# NachtElk_DBL_PowerDistribution_3V3-5V.net
KiCad netlist of a schematic drawn in EAGLE
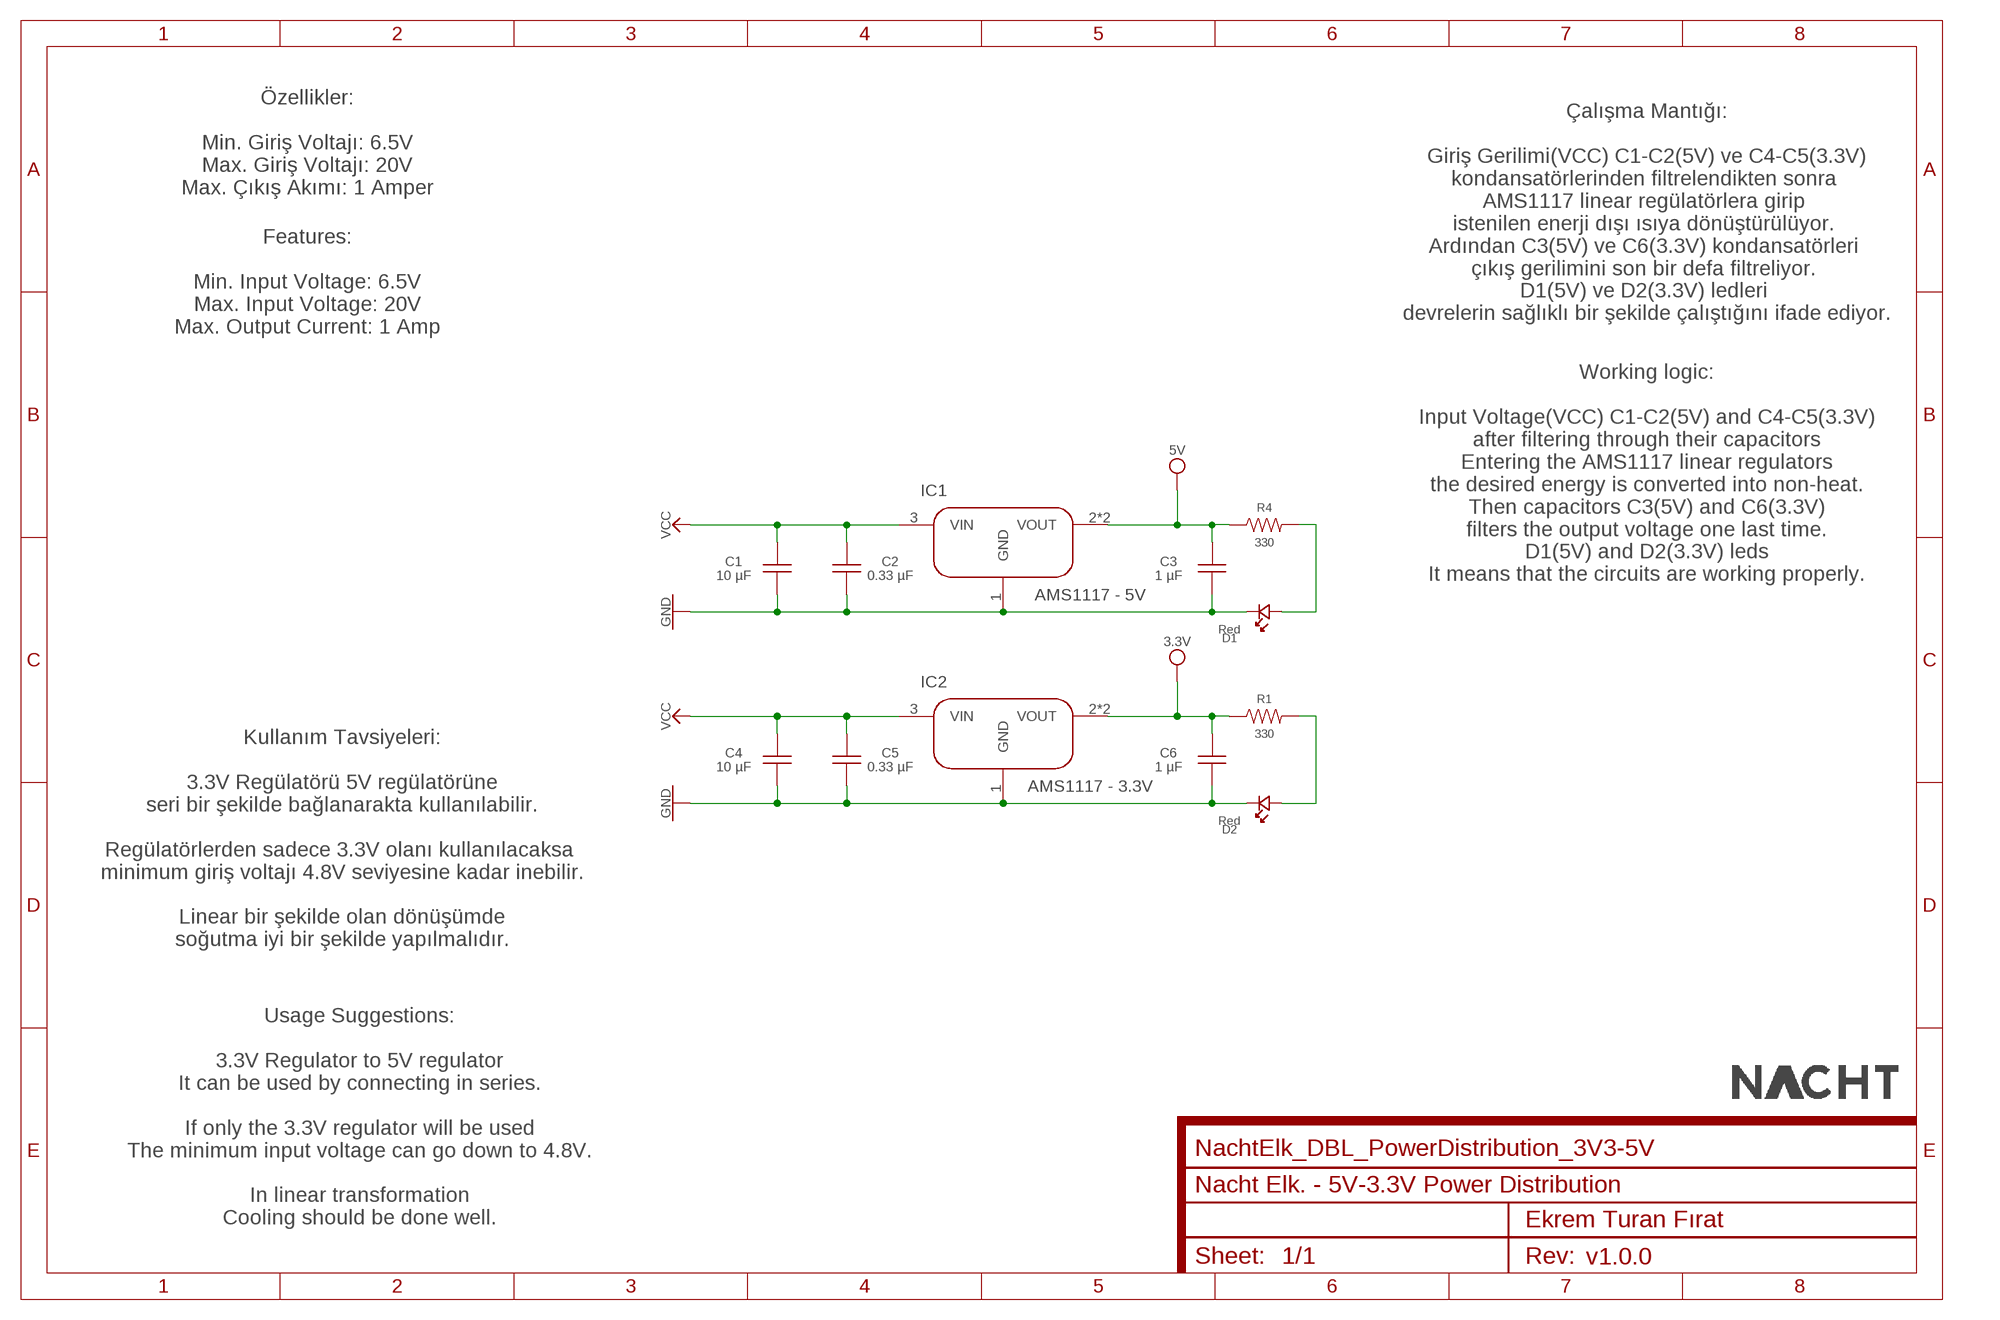
[diagram p0: schematic, sheet 1]

(export (version "E")
  (design (tool "Eeschema 10.0.6"))
  (components
    (comp (ref "C1")
      (value "10 µF")
      (footprint "eagle-import:0603")
      (fields (field (name "TOLERANCE") "10%") (field (name "VOLTAGE") "25V"))
      (libsource (lib "eagle-import") (part "NACHTELK_CAP-NONPOLAR-SMD_0603_10UF"))
    )
    (comp (ref "C2")
      (value "0.33 µF")
      (footprint "eagle-import:0603")
      (fields (field (name "TOLERANCE") "10%") (field (name "VOLTAGE") "50V"))
      (libsource (lib "eagle-import") (part "NACHTELK_CAP-NONPOLAR-SMD_0603_0.33UF"))
    )
    (comp (ref "C3")
      (value "1 µF")
      (footprint "eagle-import:0603")
      (fields (field (name "TOLERANCE") "10%") (field (name "VOLTAGE") "50V"))
      (libsource (lib "eagle-import") (part "NACHTELK_CAP-NONPOLAR-SMD_0603_1UF"))
    )
    (comp (ref "C4")
      (value "10 µF")
      (footprint "eagle-import:0603")
      (fields (field (name "TOLERANCE") "10%") (field (name "VOLTAGE") "25V"))
      (libsource (lib "eagle-import") (part "NACHTELK_CAP-NONPOLAR-SMD_0603_10UF"))
    )
    (comp (ref "C5")
      (value "0.33 µF")
      (footprint "eagle-import:0603")
      (fields (field (name "TOLERANCE") "10%") (field (name "VOLTAGE") "50V"))
      (libsource (lib "eagle-import") (part "NACHTELK_CAP-NONPOLAR-SMD_0603_0.33UF"))
    )
    (comp (ref "C6")
      (value "1 µF")
      (footprint "eagle-import:0603")
      (fields (field (name "TOLERANCE") "10%") (field (name "VOLTAGE") "50V"))
      (libsource (lib "eagle-import") (part "NACHTELK_CAP-NONPOLAR-SMD_0603_1UF"))
    )
    (comp (ref "D1")
      (value "Red")
      (footprint "eagle-import:0603_RED")
      (fields (field (name "VOLTAGE") "3.3V"))
      (libsource (lib "eagle-import") (part "NACHTELK_LED_SMD_0603_RED"))
    )
    (comp (ref "D2")
      (value "Red")
      (footprint "eagle-import:0603_RED")
      (fields (field (name "VOLTAGE") "3.3V"))
      (libsource (lib "eagle-import") (part "NACHTELK_LED_SMD_0603_RED"))
    )
    (comp (ref "IC1")
      (value "AMS1117 - 5V")
      (footprint "eagle-import:SOT-223")
      (libsource (lib "eagle-import") (part "NACHTELK_LINEAR-REG_AMS1117_5V"))
    )
    (comp (ref "IC2")
      (value "AMS1117 - 3.3V")
      (footprint "eagle-import:SOT-223")
      (libsource (lib "eagle-import") (part "NACHTELK_LINEAR-REG_AMS1117_3.3V"))
    )
    (comp (ref "R1")
      (value "330")
      (footprint "eagle-import:0603")
      (fields (field (name "POWER") "1/10W") (field (name "TOLERANCE") "%5"))
      (libsource (lib "eagle-import") (part "NACHTELK_RES-SMD_0603_330R"))
    )
    (comp (ref "R4")
      (value "330")
      (footprint "eagle-import:0603")
      (fields (field (name "POWER") "1/10W") (field (name "TOLERANCE") "%5"))
      (libsource (lib "eagle-import") (part "NACHTELK_RES-SMD_0603_330R"))
    )
    (comp (ref "U$1")
      (value "NACHTELK_AESTHETICS_NACHTELK-LOGO_2X7")
      (footprint "eagle-import:NACHTELK_LOGO_2X7")
      (libsource (lib "eagle-import") (part "NACHTELK_AESTHETICS_NACHTELK-LOGO_2X7"))
    )
  )
  (nets
    (net (code "1") (name "3.3V") (class "Default")
      (node (ref "C6") (pin "1") (pinfunction "1_1") (pintype "passive"))
      (node (ref "IC2") (pin "2") (pinfunction "VOUT_2") (pintype "output"))
      (node (ref "IC2") (pin "4") (pinfunction "VOUT_4") (pintype "output"))
      (node (ref "R1") (pin "1") (pinfunction "1_1") (pintype "passive"))
    )
    (net (code "2") (name "5V") (class "Default")
      (node (ref "C3") (pin "1") (pinfunction "1_1") (pintype "passive"))
      (node (ref "IC1") (pin "2") (pinfunction "VOUT_2") (pintype "output"))
      (node (ref "IC1") (pin "4") (pinfunction "VOUT_4") (pintype "output"))
      (node (ref "R4") (pin "1") (pinfunction "1_1") (pintype "passive"))
    )
    (net (code "3") (name "GND") (class "Default")
      (node (ref "C1") (pin "2") (pinfunction "2_2") (pintype "passive"))
      (node (ref "C2") (pin "2") (pinfunction "2_2") (pintype "passive"))
      (node (ref "C3") (pin "2") (pinfunction "2_2") (pintype "passive"))
      (node (ref "C4") (pin "2") (pinfunction "2_2") (pintype "passive"))
      (node (ref "C5") (pin "2") (pinfunction "2_2") (pintype "passive"))
      (node (ref "C6") (pin "2") (pinfunction "2_2") (pintype "passive"))
      (node (ref "D1") (pin "2") (pinfunction "KATOT_2") (pintype "passive"))
      (node (ref "D2") (pin "2") (pinfunction "KATOT_2") (pintype "passive"))
      (node (ref "IC1") (pin "1") (pinfunction "GND_1") (pintype "power_in"))
      (node (ref "IC2") (pin "1") (pinfunction "GND_1") (pintype "power_in"))
    )
    (net (code "4") (name "Net-(D1-ANOT)") (class "Default")
      (node (ref "D1") (pin "1") (pinfunction "ANOT_1") (pintype "passive"))
      (node (ref "R4") (pin "2") (pinfunction "2_2") (pintype "passive"))
    )
    (net (code "5") (name "Net-(D2-ANOT)") (class "Default")
      (node (ref "D2") (pin "1") (pinfunction "ANOT_1") (pintype "passive"))
      (node (ref "R1") (pin "2") (pinfunction "2_2") (pintype "passive"))
    )
    (net (code "6") (name "VCC") (class "Default")
      (node (ref "C1") (pin "1") (pinfunction "1_1") (pintype "passive"))
      (node (ref "C2") (pin "1") (pinfunction "1_1") (pintype "passive"))
      (node (ref "C4") (pin "1") (pinfunction "1_1") (pintype "passive"))
      (node (ref "C5") (pin "1") (pinfunction "1_1") (pintype "passive"))
      (node (ref "IC1") (pin "3") (pinfunction "VIN_3") (pintype "input"))
      (node (ref "IC2") (pin "3") (pinfunction "VIN_3") (pintype "input"))
    )
  )
)
